# DiffAmp_K-10.net
KiCad netlist of a schematic drawn in Altium Designer
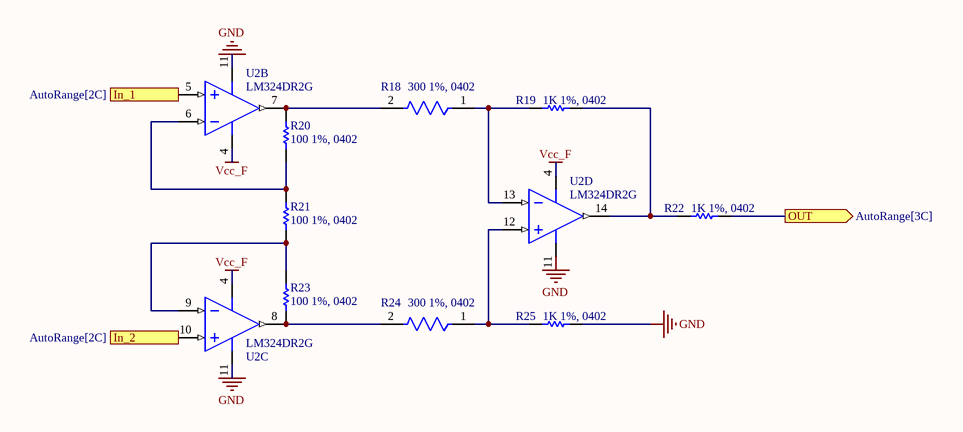
[diagram p0: DiffAmp_K-10.SchDoc]

(export (version "E")
  (design (tool "Eeschema 10.0.6"))
  (components
    (comp (ref "R18")
      (value "300 1%, 0402")
      (footprint "FP-ERJ2RK-IPC_A")
      (description "RES SMD 300 OHM 1% 1/10W 0402")
      (fields (field (name "TOLERANCE") "1%"))
      (libsource (lib "Altium Content Vault") (part "1029c3af85768c4190bb7ad29bc67b5"))
    )
    (comp (ref "R19")
      (value "1K 1%, 0402")
      (footprint "RESC1005X40X25NL05T05")
      (description "Chip Resistor, 1 KOhm, +/- 1%, 100 mW, -55 to 155 degC, 0402 (1005 Metric), RoHS, Tape and Reel")
      (fields (field (name "PARTNUMBER") "ERJ-2RKF1001X") (field (name "MANUFACTURER") "Basic Passives"))
      (libsource (lib "Altium Content Vault") (part "RES-2"))
    )
    (comp (ref "R20")
      (value "100 1%, 0402")
      (footprint "RESC1005X40X25LL05T05")
      (description "Chip Resistor, 100 Ohm, +/- 1%, 100 mW, -55 to 155 degC, 0402 (1005 Metric), RoHS, Tape and Reel")
      (fields (field (name "MANUFACTURER") "Basic Passives") (field (name "TOLERANCE") "1%"))
      (libsource (lib "Altium Content Vault") (part "RES-2"))
    )
    (comp (ref "R21")
      (value "100 1%, 0402")
      (footprint "RESC1005X40X25LL05T05")
      (description "Chip Resistor, 100 Ohm, +/- 1%, 100 mW, -55 to 155 degC, 0402 (1005 Metric), RoHS, Tape and Reel")
      (fields (field (name "MANUFACTURER") "Basic Passives") (field (name "TOLERANCE") "1%"))
      (libsource (lib "Altium Content Vault") (part "RES-2"))
    )
    (comp (ref "R22")
      (value "1K 1%, 0402")
      (footprint "RESC1005X40X25NL05T05")
      (description "Chip Resistor, 1 KOhm, +/- 1%, 100 mW, -55 to 155 degC, 0402 (1005 Metric), RoHS, Tape and Reel")
      (fields (field (name "PARTNUMBER") "ERJ-2RKF1001X") (field (name "MANUFACTURER") "Basic Passives"))
      (libsource (lib "Altium Content Vault") (part "RES-2"))
    )
    (comp (ref "R23")
      (value "100 1%, 0402")
      (footprint "RESC1005X40X25LL05T05")
      (description "Chip Resistor, 100 Ohm, +/- 1%, 100 mW, -55 to 155 degC, 0402 (1005 Metric), RoHS, Tape and Reel")
      (fields (field (name "MANUFACTURER") "Basic Passives") (field (name "TOLERANCE") "1%"))
      (libsource (lib "Altium Content Vault") (part "RES-2"))
    )
    (comp (ref "R24")
      (value "300 1%, 0402")
      (footprint "FP-ERJ2RK-IPC_A")
      (description "RES SMD 300 OHM 1% 1/10W 0402")
      (fields (field (name "TOLERANCE") "1%"))
      (libsource (lib "Altium Content Vault") (part "1029c3af85768c4190bb7ad29bc67b5"))
    )
    (comp (ref "R25")
      (value "1K 1%, 0402")
      (footprint "RESC1005X40X25NL05T05")
      (description "Chip Resistor, 1 KOhm, +/- 1%, 100 mW, -55 to 155 degC, 0402 (1005 Metric), RoHS, Tape and Reel")
      (fields (field (name "PARTNUMBER") "ERJ-2RKF1001X") (field (name "MANUFACTURER") "Basic Passives"))
      (libsource (lib "Altium Content Vault") (part "RES-2"))
    )
    (comp (ref "U2")
      (value "LM324DR2G")
      (footprint "ONSC-SOIC-14-751A-03_V")
      (fields (field (name "MANUFACTURER") "On Semiconductor"))
      (libsource (lib "Altium Content Vault") (part "ONSC-LM224_324_2902_NCV2902-14"))
    )
  )
  (nets
    (net (code "1") (name "/In_1") (class "Default")
      (node (ref "U2") (pin "5") (pinfunction "IN2+_5") (pintype "input"))
    )
    (net (code "2") (name "/In_2") (class "Default")
      (node (ref "U2") (pin "10") (pinfunction "IN3+_10") (pintype "input"))
    )
    (net (code "3") (name "/OUT") (class "Default")
      (node (ref "R22") (pin "2") (pinfunction "2_2") (pintype "passive"))
    )
    (net (code "4") (name "GND") (class "Default")
      (node (ref "R25") (pin "2") (pinfunction "2_2") (pintype "passive"))
      (node (ref "U2") (pin "11") (pinfunction "VEE/GND_11") (pintype "power_in"))
    )
    (net (code "5") (name "Net-(U2B-IN2-)") (class "Default")
      (node (ref "R20") (pin "1") (pinfunction "1_1") (pintype "passive"))
      (node (ref "R21") (pin "2") (pinfunction "2_2") (pintype "passive"))
      (node (ref "U2") (pin "6") (pinfunction "IN2-_6") (pintype "input"))
    )
    (net (code "6") (name "Net-(U2B-OUT2)") (class "Default")
      (node (ref "R18") (pin "2") (pinfunction "2_2") (pintype "passive"))
      (node (ref "R20") (pin "2") (pinfunction "2_2") (pintype "passive"))
      (node (ref "U2") (pin "7") (pinfunction "OUT2_7") (pintype "output"))
    )
    (net (code "7") (name "Net-(U2C-IN3-)") (class "Default")
      (node (ref "R21") (pin "1") (pinfunction "1_1") (pintype "passive"))
      (node (ref "R23") (pin "2") (pinfunction "2_2") (pintype "passive"))
      (node (ref "U2") (pin "9") (pinfunction "IN3-_9") (pintype "input"))
    )
    (net (code "8") (name "Net-(U2C-OUT3)") (class "Default")
      (node (ref "R23") (pin "1") (pinfunction "1_1") (pintype "passive"))
      (node (ref "R24") (pin "2") (pinfunction "2_2") (pintype "passive"))
      (node (ref "U2") (pin "8") (pinfunction "OUT3_8") (pintype "output"))
    )
    (net (code "9") (name "Net-(U2D-IN4+)") (class "Default")
      (node (ref "R24") (pin "1") (pinfunction "1_1") (pintype "passive"))
      (node (ref "R25") (pin "1") (pinfunction "1_1") (pintype "passive"))
      (node (ref "U2") (pin "12") (pinfunction "IN4+_12") (pintype "input"))
    )
    (net (code "10") (name "Net-(U2D-IN4-)") (class "Default")
      (node (ref "R18") (pin "1") (pinfunction "1_1") (pintype "passive"))
      (node (ref "R19") (pin "1") (pinfunction "1_1") (pintype "passive"))
      (node (ref "U2") (pin "13") (pinfunction "IN4-_13") (pintype "input"))
    )
    (net (code "11") (name "Net-(U2D-OUT4)") (class "Default")
      (node (ref "R19") (pin "2") (pinfunction "2_2") (pintype "passive"))
      (node (ref "R22") (pin "1") (pinfunction "1_1") (pintype "passive"))
      (node (ref "U2") (pin "14") (pinfunction "OUT4_14") (pintype "output"))
    )
    (net (code "12") (name "Vcc_F") (class "Default")
      (node (ref "U2") (pin "4") (pinfunction "VCC_4") (pintype "power_in"))
    )
    (net (code "13") (name "unconnected-(U2D-VEE{slash}GND-Pad11)") (class "Default")
      (node (ref "U2") (pin "11") (pinfunction "VEE/GND_11") (pintype "power_in"))
    )
  )
)
